# EasyEDA-tinySpeak_2026-02-18.net
KiCad netlist of a schematic drawn in EasyEDA Pro
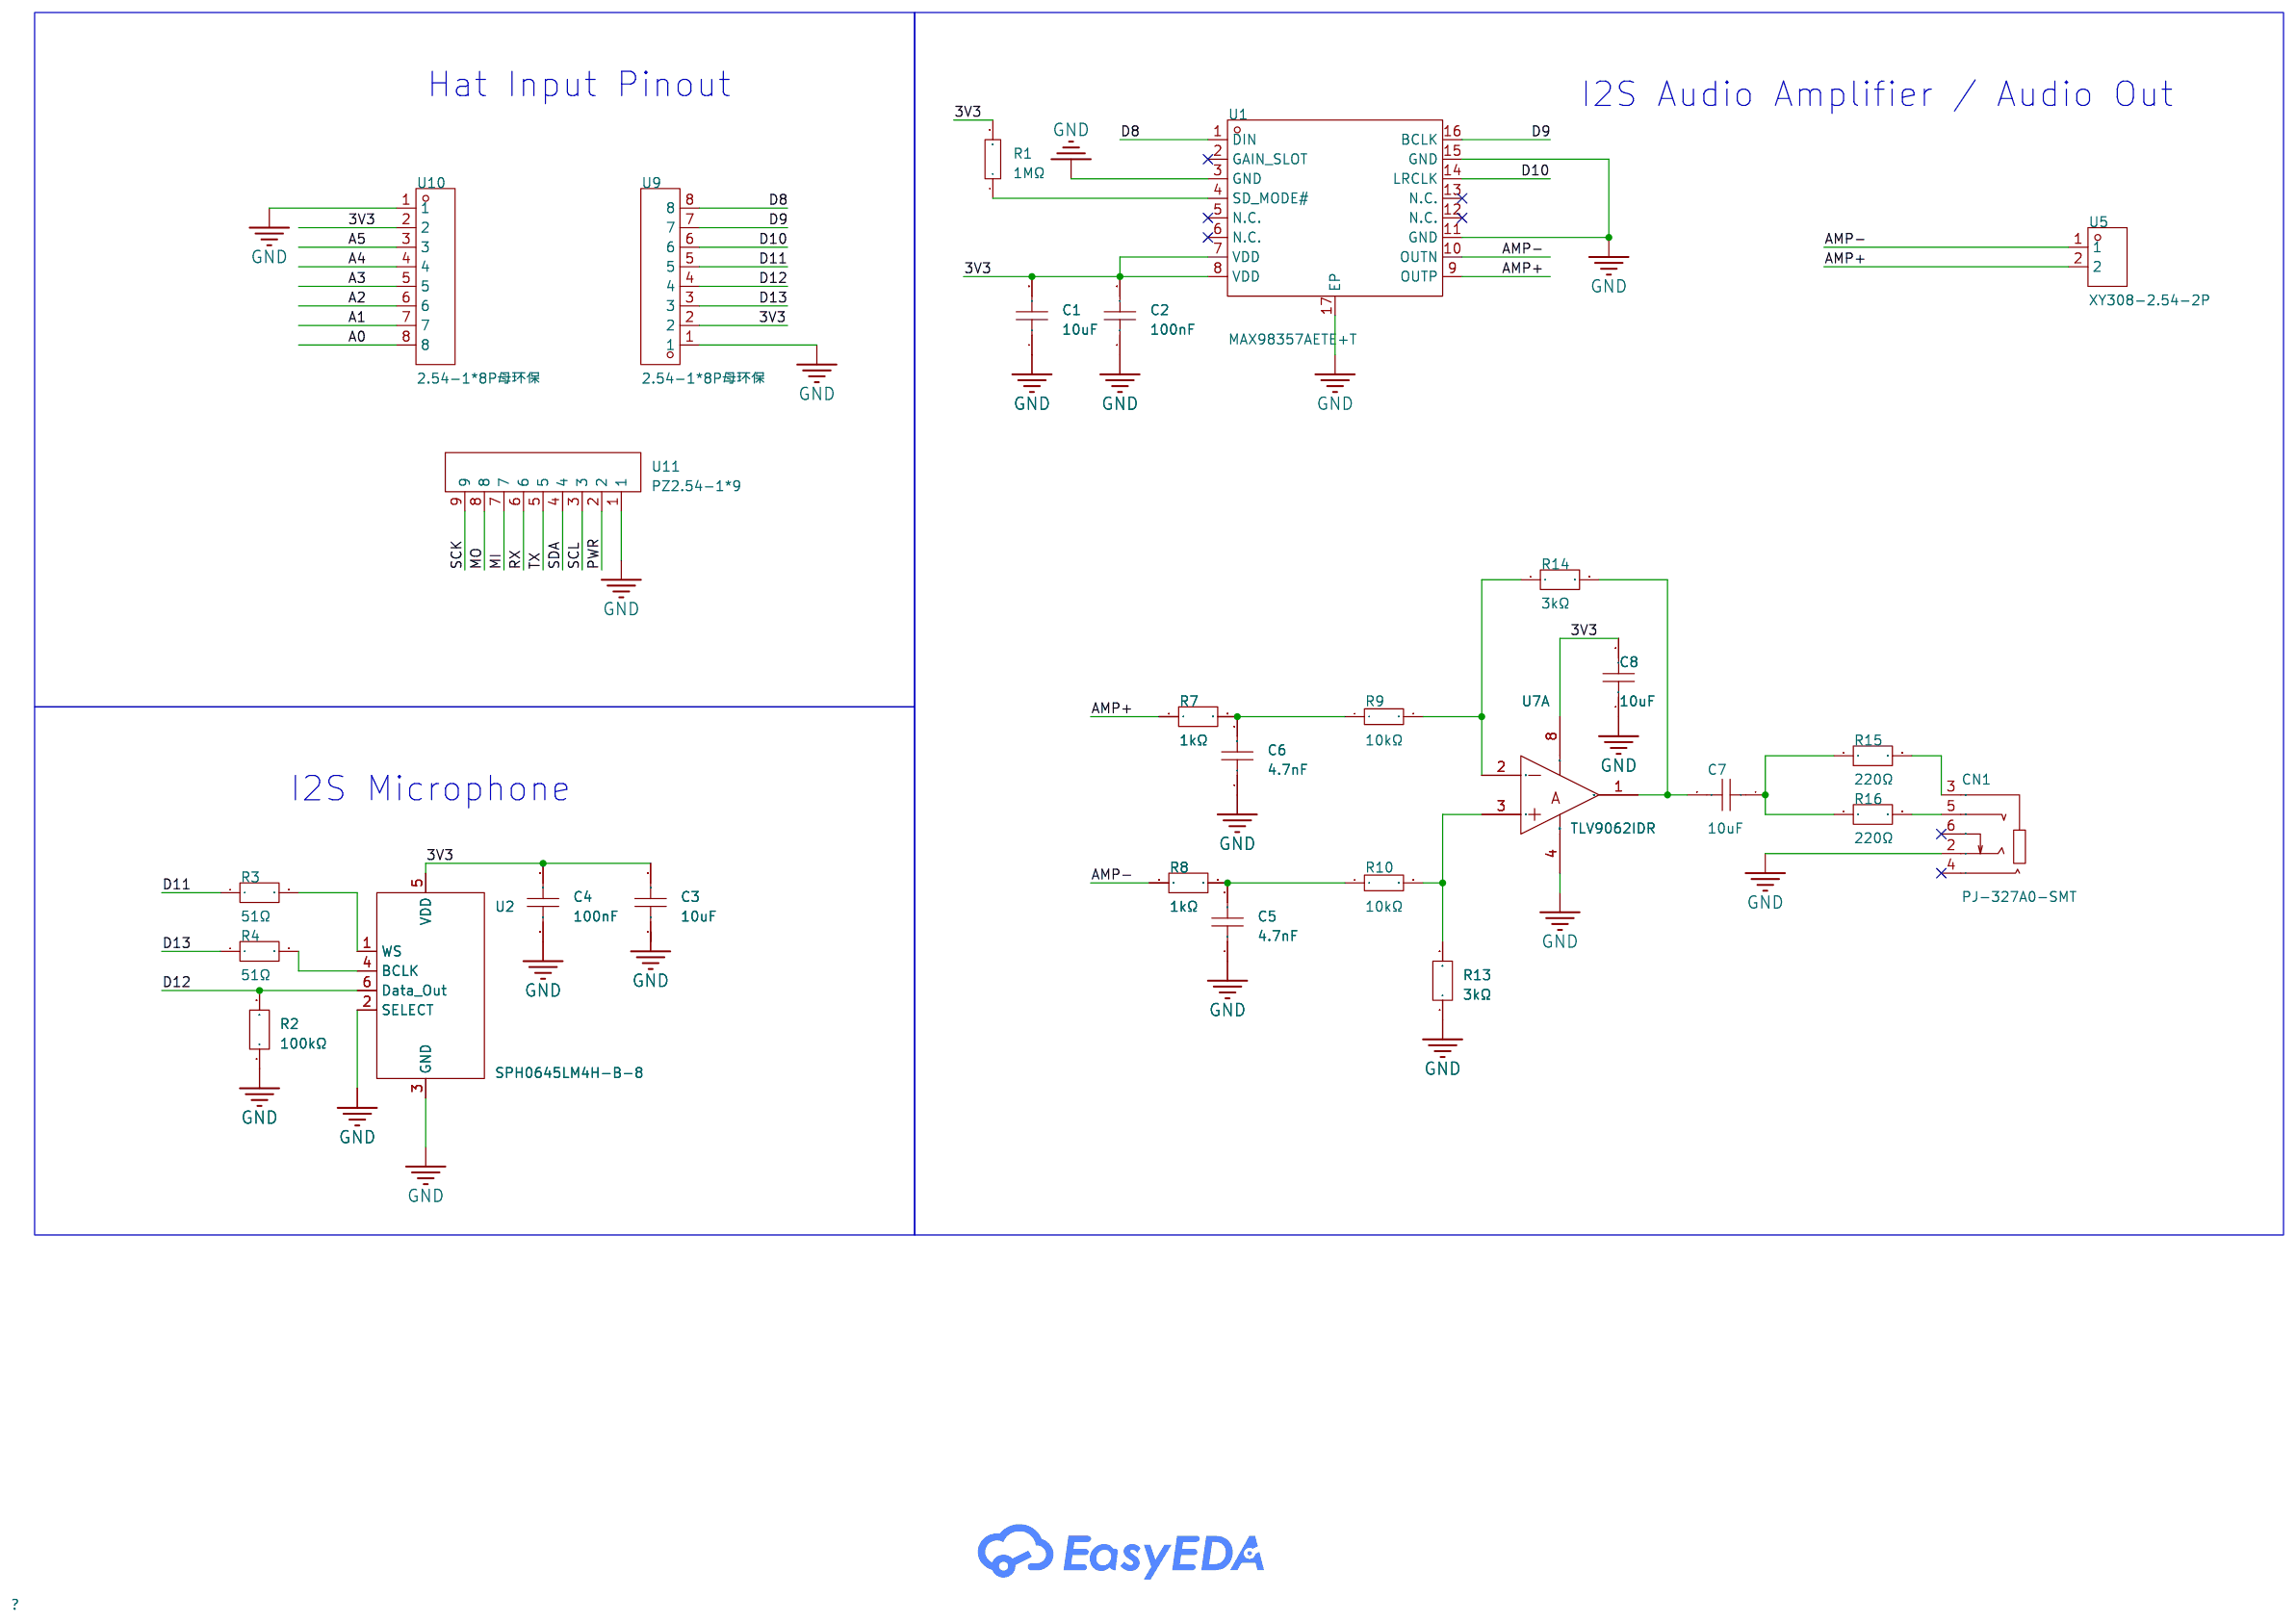
[diagram p0: schematic sheet]

(export (version "E")
  (design (tool "Eeschema 10.0.6"))
  (components
    (comp (ref "C1")
      (value "10uF")
      (footprint "easyedapro:C0603")
      (description "Capacitance:10uF Tolerance:±10% Tolerance:±10% Voltage Rating:16V Temperature Coefficient:X5R")
      (fields
        (field (name "Manufacturer Part") "TCC0603X5R106K160CT")
        (field (name "Manufacturer") "CCTC(三环)")
      )
      (libsource (lib "easyedapro") (part "TCC0603X5R106K160CT"))
    )
    (comp (ref "C2")
      (value "100nF")
      (footprint "easyedapro:C0603")
      (description "Capacitance:100nF Tolerance:±10% Tolerance:±10% Voltage Rating:50V Temperature Coefficient:X7R")
      (fields
        (field (name "Manufacturer Part") "CC0603KRX7R9BB104")
        (field (name "Manufacturer") "YAGEO(国巨)")
      )
      (libsource (lib "easyedapro") (part "CC0603KRX7R9BB104"))
    )
    (comp (ref "C3")
      (value "10uF")
      (footprint "easyedapro:C0603")
      (description "Capacitance:10uF Tolerance:±10% Tolerance:±10% Voltage Rating:16V Temperature Coefficient:X5R")
      (fields
        (field (name "Manufacturer Part") "TCC0603X5R106K160CT")
        (field (name "Manufacturer") "CCTC(三环)")
      )
      (libsource (lib "easyedapro") (part "TCC0603X5R106K160CT"))
    )
    (comp (ref "C4")
      (value "100nF")
      (footprint "easyedapro:C0603")
      (description "Capacitance:100nF Tolerance:±10% Tolerance:±10% Voltage Rating:50V Temperature Coefficient:X7R")
      (fields
        (field (name "Manufacturer Part") "CC0603KRX7R9BB104")
        (field (name "Manufacturer") "YAGEO(国巨)")
      )
      (libsource (lib "easyedapro") (part "CC0603KRX7R9BB104"))
    )
    (comp (ref "C5")
      (value "4.7nF")
      (footprint "easyedapro:C0603")
      (description "Capacitance:4.7nF Tolerance:±5% Tolerance:±5% Voltage Rating:16V Temperature Coefficient:C0G")
      (fields (field (name "Manufacturer Part") "FN18N472J160PBG") (field (name "Manufacturer") "PSA(信昌电陶)"))
      (libsource (lib "easyedapro") (part "FN18N472J160PBG"))
    )
    (comp (ref "C6")
      (value "4.7nF")
      (footprint "easyedapro:C0603")
      (description "Capacitance:4.7nF Tolerance:±5% Tolerance:±5% Voltage Rating:16V Temperature Coefficient:C0G")
      (fields (field (name "Manufacturer Part") "FN18N472J160PBG") (field (name "Manufacturer") "PSA(信昌电陶)"))
      (libsource (lib "easyedapro") (part "FN18N472J160PBG"))
    )
    (comp (ref "C7")
      (value "10uF")
      (footprint "easyedapro:C0603")
      (description "Capacitance:10uF Tolerance:±10% Tolerance:±10% Voltage Rating:16V Temperature Coefficient:X5R")
      (fields
        (field (name "Manufacturer Part") "TCC0603X5R106K160CT")
        (field (name "Manufacturer") "CCTC(三环)")
      )
      (libsource (lib "easyedapro") (part "TCC0603X5R106K160CT"))
    )
    (comp (ref "C8")
      (value "10uF")
      (footprint "easyedapro:C0603")
      (description "Capacitance:10uF Tolerance:±10% Tolerance:±10% Voltage Rating:16V Temperature Coefficient:X5R")
      (fields
        (field (name "Manufacturer Part") "TCC0603X5R106K160CT")
        (field (name "Manufacturer") "CCTC(三环)")
      )
      (libsource (lib "easyedapro") (part "TCC0603X5R106K160CT"))
    )
    (comp (ref "CN1")
      (value "PJ-327A0-SMT")
      (footprint "easyedapro:AUDIO-SMD_PJ-327A0-SMT")
      (fields (field (name "Manufacturer") "XKB Connection(中国星坤)"))
      (libsource (lib "easyedapro") (part "PJ-327A0-SMT"))
    )
    (comp (ref "R1")
      (value "1MΩ")
      (footprint "easyedapro:R0603")
      (fields (field (name "Manufacturer Part") "RC0603FR-071ML") (field (name "Manufacturer") "YAGEO(国巨)"))
      (libsource (lib "easyedapro") (part "RC0603FR-071ML"))
    )
    (comp (ref "R2")
      (value "100kΩ")
      (footprint "easyedapro:R0603")
      (fields (field (name "Manufacturer Part") "FRC0603F1003TS") (field (name "Manufacturer") "FOJAN(富捷)"))
      (libsource (lib "easyedapro") (part "FRC0603F1003TS"))
    )
    (comp (ref "R3")
      (value "51Ω")
      (footprint "easyedapro:R0603")
      (fields (field (name "Manufacturer Part") "FRC0603J510 TS") (field (name "Manufacturer") "FOJAN(富捷)"))
      (libsource (lib "easyedapro") (part "FRC0603J510 TS"))
    )
    (comp (ref "R4")
      (value "51Ω")
      (footprint "easyedapro:R0603")
      (fields (field (name "Manufacturer Part") "FRC0603J510 TS") (field (name "Manufacturer") "FOJAN(富捷)"))
      (libsource (lib "easyedapro") (part "FRC0603J510 TS"))
    )
    (comp (ref "R7")
      (value "1kΩ")
      (footprint "easyedapro:R0603")
      (fields (field (name "Manufacturer Part") "FRR0603J102 TS") (field (name "Manufacturer") "FOJAN(富捷)"))
      (libsource (lib "easyedapro") (part "FRR0603J102 TS"))
    )
    (comp (ref "R8")
      (value "1kΩ")
      (footprint "easyedapro:R0603")
      (fields (field (name "Manufacturer Part") "FRR0603J102 TS") (field (name "Manufacturer") "FOJAN(富捷)"))
      (libsource (lib "easyedapro") (part "FRR0603J102 TS"))
    )
    (comp (ref "R9")
      (value "10kΩ")
      (footprint "easyedapro:R0603")
      (fields (field (name "Manufacturer Part") "RC0603FR-0710KL") (field (name "Manufacturer") "YAGEO(国巨)"))
      (libsource (lib "easyedapro") (part "RC0603FR-0710KL"))
    )
    (comp (ref "R10")
      (value "10kΩ")
      (footprint "easyedapro:R0603")
      (fields (field (name "Manufacturer Part") "RC0603FR-0710KL") (field (name "Manufacturer") "YAGEO(国巨)"))
      (libsource (lib "easyedapro") (part "RC0603FR-0710KL"))
    )
    (comp (ref "R13")
      (value "3kΩ")
      (footprint "easyedapro:R0603")
      (fields (field (name "Manufacturer Part") "FRC0603J302 TS") (field (name "Manufacturer") "FOJAN(富捷)"))
      (libsource (lib "easyedapro") (part "FRC0603J302 TS"))
    )
    (comp (ref "R14")
      (value "3kΩ")
      (footprint "easyedapro:R0603")
      (fields (field (name "Manufacturer Part") "FRC0603J302 TS") (field (name "Manufacturer") "FOJAN(富捷)"))
      (libsource (lib "easyedapro") (part "FRC0603J302 TS"))
    )
    (comp (ref "R15")
      (value "220Ω")
      (footprint "easyedapro:R0603")
      (fields (field (name "Manufacturer Part") "FRC0603F2200TS") (field (name "Manufacturer") "FOJAN(富捷)"))
      (libsource (lib "easyedapro") (part "FRC0603F2200TS"))
    )
    (comp (ref "R16")
      (value "220Ω")
      (footprint "easyedapro:R0603")
      (fields (field (name "Manufacturer Part") "FRC0603F2200TS") (field (name "Manufacturer") "FOJAN(富捷)"))
      (libsource (lib "easyedapro") (part "FRC0603F2200TS"))
    )
    (comp (ref "U1")
      (value "MAX98357AETE+T")
      (footprint "easyedapro:TQFN-16_L3.0-W3.0-P0.50-BL-EP1.5")
      (fields (field (name "Manufacturer") "ADI(亚德诺)/MAXIM(美信)"))
      (libsource (lib "easyedapro") (part "MAX98357AETE+T"))
    )
    (comp (ref "U2")
      (value "SPH0645LM4H-B-8")
      (footprint "easyedapro:MIC-SMD_6P-L3.5-W2.7-P0.90-BL")
      (fields (field (name "Manufacturer") "Knowles(楼氏)"))
      (libsource (lib "easyedapro") (part "SPH0645LM4H-B-8"))
    )
    (comp (ref "U5")
      (value "XY308-2.54-2P")
      (footprint "easyedapro:CONN-TH_XY308-2.54-2P")
      (fields (field (name "Manufacturer") "XINLAIYA(新莱亚)"))
      (libsource (lib "easyedapro") (part "XY308-2.54-2P"))
    )
    (comp (ref "U7")
      (value "TLV9062IDR")
      (footprint "easyedapro:SOIC-8_L5.0-W4.0-P1.27-LS6.0-BL")
      (fields (field (name "Manufacturer") "TI(德州仪器)"))
      (libsource (lib "easyedapro") (part "TLV9062IDR"))
    )
    (comp (ref "U9")
      (value "2.54-1*8P母环保")
      (fields (field (name "Manufacturer") "BOOMELE(博穆精密)"))
      (libsource (lib "easyedapro") (part "2.54-1*8"))
    )
    (comp (ref "U10")
      (value "2.54-1*8P母环保")
      (fields (field (name "Manufacturer") "BOOMELE(博穆精密)"))
      (libsource (lib "easyedapro") (part "2.54-1*8"))
    )
    (comp (ref "U11")
      (value "PZ2.54-1*9")
      (footprint "easyedapro:HDR-TH_9P-P2.54-V-M")
      (fields (field (name "Manufacturer") "ZHOURI(洲日)"))
      (libsource (lib "easyedapro") (part "PZ2.54-1*9"))
    )
  )
  (nets
    (net (code "1") (name "/3V3") (class "Default")
      (node (ref "C1") (pin "2") (pinfunction "2_2") (pintype "unspecified"))
      (node (ref "C2") (pin "2") (pinfunction "2_2") (pintype "unspecified"))
      (node (ref "C3") (pin "2") (pinfunction "2_2") (pintype "unspecified"))
      (node (ref "C4") (pin "2") (pinfunction "2_2") (pintype "unspecified"))
      (node (ref "C8") (pin "2") (pinfunction "2_2") (pintype "unspecified"))
      (node (ref "R1") (pin "2") (pinfunction "2_2") (pintype "input"))
      (node (ref "U1") (pin "7") (pinfunction "VDD_7") (pintype "unspecified"))
      (node (ref "U1") (pin "8") (pinfunction "VDD_8") (pintype "unspecified"))
      (node (ref "U10") (pin "2") (pinfunction "2_2") (pintype "unspecified"))
      (node (ref "U2") (pin "5") (pinfunction "VDD_5") (pintype "unspecified"))
      (node (ref "U7") (pin "8") (pinfunction "VCC_8") (pintype "unspecified"))
      (node (ref "U9") (pin "2") (pinfunction "2_2") (pintype "unspecified"))
    )
    (net (code "2") (name "/A0") (class "Default")
      (node (ref "U10") (pin "8") (pinfunction "8_8") (pintype "unspecified"))
    )
    (net (code "3") (name "/A1") (class "Default")
      (node (ref "U10") (pin "7") (pinfunction "7_7") (pintype "unspecified"))
    )
    (net (code "4") (name "/A2") (class "Default")
      (node (ref "U10") (pin "6") (pinfunction "6_6") (pintype "unspecified"))
    )
    (net (code "5") (name "/A3") (class "Default")
      (node (ref "U10") (pin "5") (pinfunction "5_5") (pintype "unspecified"))
    )
    (net (code "6") (name "/A4") (class "Default")
      (node (ref "U10") (pin "4") (pinfunction "4_4") (pintype "unspecified"))
    )
    (net (code "7") (name "/A5") (class "Default")
      (node (ref "U10") (pin "3") (pinfunction "3_3") (pintype "unspecified"))
    )
    (net (code "8") (name "/AMP+") (class "Default")
      (node (ref "R7") (pin "1") (pinfunction "1_1") (pintype "unspecified"))
      (node (ref "U1") (pin "9") (pinfunction "OUTP_9") (pintype "unspecified"))
      (node (ref "U5") (pin "2") (pinfunction "2_2") (pintype "unspecified"))
    )
    (net (code "9") (name "/AMP-") (class "Default")
      (node (ref "R8") (pin "1") (pinfunction "1_1") (pintype "unspecified"))
      (node (ref "U1") (pin "10") (pinfunction "OUTN_10") (pintype "unspecified"))
      (node (ref "U5") (pin "1") (pinfunction "1_1") (pintype "unspecified"))
    )
    (net (code "10") (name "/D8") (class "Default")
      (node (ref "U1") (pin "1") (pinfunction "DIN_1") (pintype "unspecified"))
      (node (ref "U9") (pin "8") (pinfunction "8_8") (pintype "unspecified"))
    )
    (net (code "11") (name "/D9") (class "Default")
      (node (ref "U1") (pin "16") (pinfunction "BCLK_16") (pintype "unspecified"))
      (node (ref "U9") (pin "7") (pinfunction "7_7") (pintype "unspecified"))
    )
    (net (code "12") (name "/D10") (class "Default")
      (node (ref "U1") (pin "14") (pinfunction "LRCLK_14") (pintype "unspecified"))
      (node (ref "U9") (pin "6") (pinfunction "6_6") (pintype "unspecified"))
    )
    (net (code "13") (name "/D11") (class "Default")
      (node (ref "R3") (pin "1") (pinfunction "1_1") (pintype "unspecified"))
      (node (ref "U9") (pin "5") (pinfunction "5_5") (pintype "unspecified"))
    )
    (net (code "14") (name "/D12") (class "Default")
      (node (ref "R2") (pin "2") (pinfunction "2_2") (pintype "unspecified"))
      (node (ref "U2") (pin "6") (pinfunction "Data_Out_6") (pintype "unspecified"))
      (node (ref "U9") (pin "4") (pinfunction "4_4") (pintype "unspecified"))
    )
    (net (code "15") (name "/D13") (class "Default")
      (node (ref "R4") (pin "1") (pinfunction "1_1") (pintype "unspecified"))
      (node (ref "U9") (pin "3") (pinfunction "3_3") (pintype "unspecified"))
    )
    (net (code "16") (name "/MI") (class "Default")
      (node (ref "U11") (pin "7") (pinfunction "7_7") (pintype "unspecified"))
    )
    (net (code "17") (name "/MO") (class "Default")
      (node (ref "U11") (pin "8") (pinfunction "8_8") (pintype "unspecified"))
    )
    (net (code "18") (name "/PWR") (class "Default")
      (node (ref "U11") (pin "2") (pinfunction "2_2") (pintype "unspecified"))
    )
    (net (code "19") (name "/RX") (class "Default")
      (node (ref "U11") (pin "6") (pinfunction "6_6") (pintype "unspecified"))
    )
    (net (code "20") (name "/SCK") (class "Default")
      (node (ref "U11") (pin "9") (pinfunction "9_9") (pintype "unspecified"))
    )
    (net (code "21") (name "/SCL") (class "Default")
      (node (ref "U11") (pin "3") (pinfunction "3_3") (pintype "unspecified"))
    )
    (net (code "22") (name "/SDA") (class "Default")
      (node (ref "U11") (pin "4") (pinfunction "4_4") (pintype "unspecified"))
    )
    (net (code "23") (name "/TX") (class "Default")
      (node (ref "U11") (pin "5") (pinfunction "5_5") (pintype "unspecified"))
    )
    (net (code "24") (name "GND") (class "Default")
      (node (ref "C1") (pin "1") (pinfunction "1_1") (pintype "unspecified"))
      (node (ref "C2") (pin "1") (pinfunction "1_1") (pintype "unspecified"))
      (node (ref "C3") (pin "1") (pinfunction "1_1") (pintype "unspecified"))
      (node (ref "C4") (pin "1") (pinfunction "1_1") (pintype "unspecified"))
      (node (ref "C5") (pin "1") (pinfunction "1_1") (pintype "unspecified"))
      (node (ref "C6") (pin "1") (pinfunction "1_1") (pintype "unspecified"))
      (node (ref "C8") (pin "1") (pinfunction "1_1") (pintype "unspecified"))
      (node (ref "CN1") (pin "2") (pinfunction "2_2") (pintype "unspecified"))
      (node (ref "R13") (pin "1") (pinfunction "1_1") (pintype "unspecified"))
      (node (ref "R2") (pin "1") (pinfunction "1_1") (pintype "unspecified"))
      (node (ref "U1") (pin "11") (pinfunction "GND_11") (pintype "unspecified"))
      (node (ref "U1") (pin "15") (pinfunction "GND_15") (pintype "unspecified"))
      (node (ref "U1") (pin "17") (pinfunction "EP_17") (pintype "unspecified"))
      (node (ref "U1") (pin "3") (pinfunction "GND_3") (pintype "unspecified"))
      (node (ref "U10") (pin "1") (pinfunction "1_1") (pintype "unspecified"))
      (node (ref "U11") (pin "1") (pinfunction "1_1") (pintype "unspecified"))
      (node (ref "U2") (pin "2") (pinfunction "SELECT_2") (pintype "unspecified"))
      (node (ref "U2") (pin "3") (pinfunction "GND_3") (pintype "unspecified"))
      (node (ref "U7") (pin "4") (pinfunction "VEE/GND_4") (pintype "unspecified"))
      (node (ref "U9") (pin "1") (pinfunction "1_1") (pintype "unspecified"))
    )
    (net (code "25") (name "Net-(C5-Pad2)") (class "Default")
      (node (ref "C5") (pin "2") (pinfunction "2_2") (pintype "unspecified"))
      (node (ref "R10") (pin "1") (pinfunction "1_1") (pintype "input"))
      (node (ref "R8") (pin "2") (pinfunction "2_2") (pintype "unspecified"))
    )
    (net (code "26") (name "Net-(C6-Pad2)") (class "Default")
      (node (ref "C6") (pin "2") (pinfunction "2_2") (pintype "unspecified"))
      (node (ref "R7") (pin "2") (pinfunction "2_2") (pintype "unspecified"))
      (node (ref "R9") (pin "1") (pinfunction "1_1") (pintype "input"))
    )
    (net (code "27") (name "Net-(C7-Pad1)") (class "Default")
      (node (ref "C7") (pin "1") (pinfunction "1_1") (pintype "unspecified"))
      (node (ref "R15") (pin "1") (pinfunction "1_1") (pintype "unspecified"))
      (node (ref "R16") (pin "1") (pinfunction "1_1") (pintype "unspecified"))
    )
    (net (code "28") (name "Net-(CN1-Pad3)") (class "Default")
      (node (ref "CN1") (pin "3") (pinfunction "3_3") (pintype "unspecified"))
      (node (ref "R15") (pin "2") (pinfunction "2_2") (pintype "unspecified"))
    )
    (net (code "29") (name "Net-(CN1-Pad5)") (class "Default")
      (node (ref "CN1") (pin "5") (pinfunction "5_5") (pintype "unspecified"))
      (node (ref "R16") (pin "2") (pinfunction "2_2") (pintype "unspecified"))
    )
    (net (code "30") (name "Net-(U1-SD_MODE#)") (class "Default")
      (node (ref "R1") (pin "1") (pinfunction "1_1") (pintype "input"))
      (node (ref "U1") (pin "4") (pinfunction "SD_MODE#_4") (pintype "unspecified"))
    )
    (net (code "31") (name "Net-(U2-BCLK)") (class "Default")
      (node (ref "R4") (pin "2") (pinfunction "2_2") (pintype "unspecified"))
      (node (ref "U2") (pin "4") (pinfunction "BCLK_4") (pintype "unspecified"))
    )
    (net (code "32") (name "Net-(U2-WS)") (class "Default")
      (node (ref "R3") (pin "2") (pinfunction "2_2") (pintype "unspecified"))
      (node (ref "U2") (pin "1") (pinfunction "WS_1") (pintype "unspecified"))
    )
    (net (code "33") (name "Net-(U7A-INA+)") (class "Default")
      (node (ref "R10") (pin "2") (pinfunction "2_2") (pintype "input"))
      (node (ref "R13") (pin "2") (pinfunction "2_2") (pintype "unspecified"))
      (node (ref "U7") (pin "3") (pinfunction "INA+_3") (pintype "unspecified"))
    )
    (net (code "34") (name "Net-(U7A-INA-)") (class "Default")
      (node (ref "R14") (pin "1") (pinfunction "1_1") (pintype "unspecified"))
      (node (ref "R9") (pin "2") (pinfunction "2_2") (pintype "input"))
      (node (ref "U7") (pin "2") (pinfunction "INA-_2") (pintype "unspecified"))
    )
    (net (code "35") (name "Net-(U7A-OUTA)") (class "Default")
      (node (ref "C7") (pin "2") (pinfunction "2_2") (pintype "unspecified"))
      (node (ref "R14") (pin "2") (pinfunction "2_2") (pintype "unspecified"))
      (node (ref "U7") (pin "1") (pinfunction "OUTA_1") (pintype "output"))
    )
    (net (code "36") (name "unconnected-(CN1-Pad4)") (class "Default")
      (node (ref "CN1") (pin "4") (pinfunction "4_4") (pintype "unspecified+no_connect"))
    )
    (net (code "37") (name "unconnected-(CN1-Pad6)") (class "Default")
      (node (ref "CN1") (pin "6") (pinfunction "6_6") (pintype "unspecified+no_connect"))
    )
    (net (code "38") (name "unconnected-(U1-GAIN_SLOT-Pad2)") (class "Default")
      (node (ref "U1") (pin "2") (pinfunction "GAIN_SLOT_2") (pintype "unspecified+no_connect"))
    )
    (net (code "39") (name "unconnected-(U1-N.C.-Pad5)") (class "Default")
      (node (ref "U1") (pin "5") (pinfunction "N.C._5") (pintype "unspecified+no_connect"))
    )
    (net (code "40") (name "unconnected-(U1-N.C.-Pad6)") (class "Default")
      (node (ref "U1") (pin "6") (pinfunction "N.C._6") (pintype "unspecified+no_connect"))
    )
    (net (code "41") (name "unconnected-(U1-N.C.-Pad12)") (class "Default")
      (node (ref "U1") (pin "12") (pinfunction "N.C._12") (pintype "unspecified+no_connect"))
    )
    (net (code "42") (name "unconnected-(U1-N.C.-Pad13)") (class "Default")
      (node (ref "U1") (pin "13") (pinfunction "N.C._13") (pintype "unspecified+no_connect"))
    )
  )
)
